# OPEnS-RTC-1_0.net
KiCad netlist of a schematic drawn in EAGLE
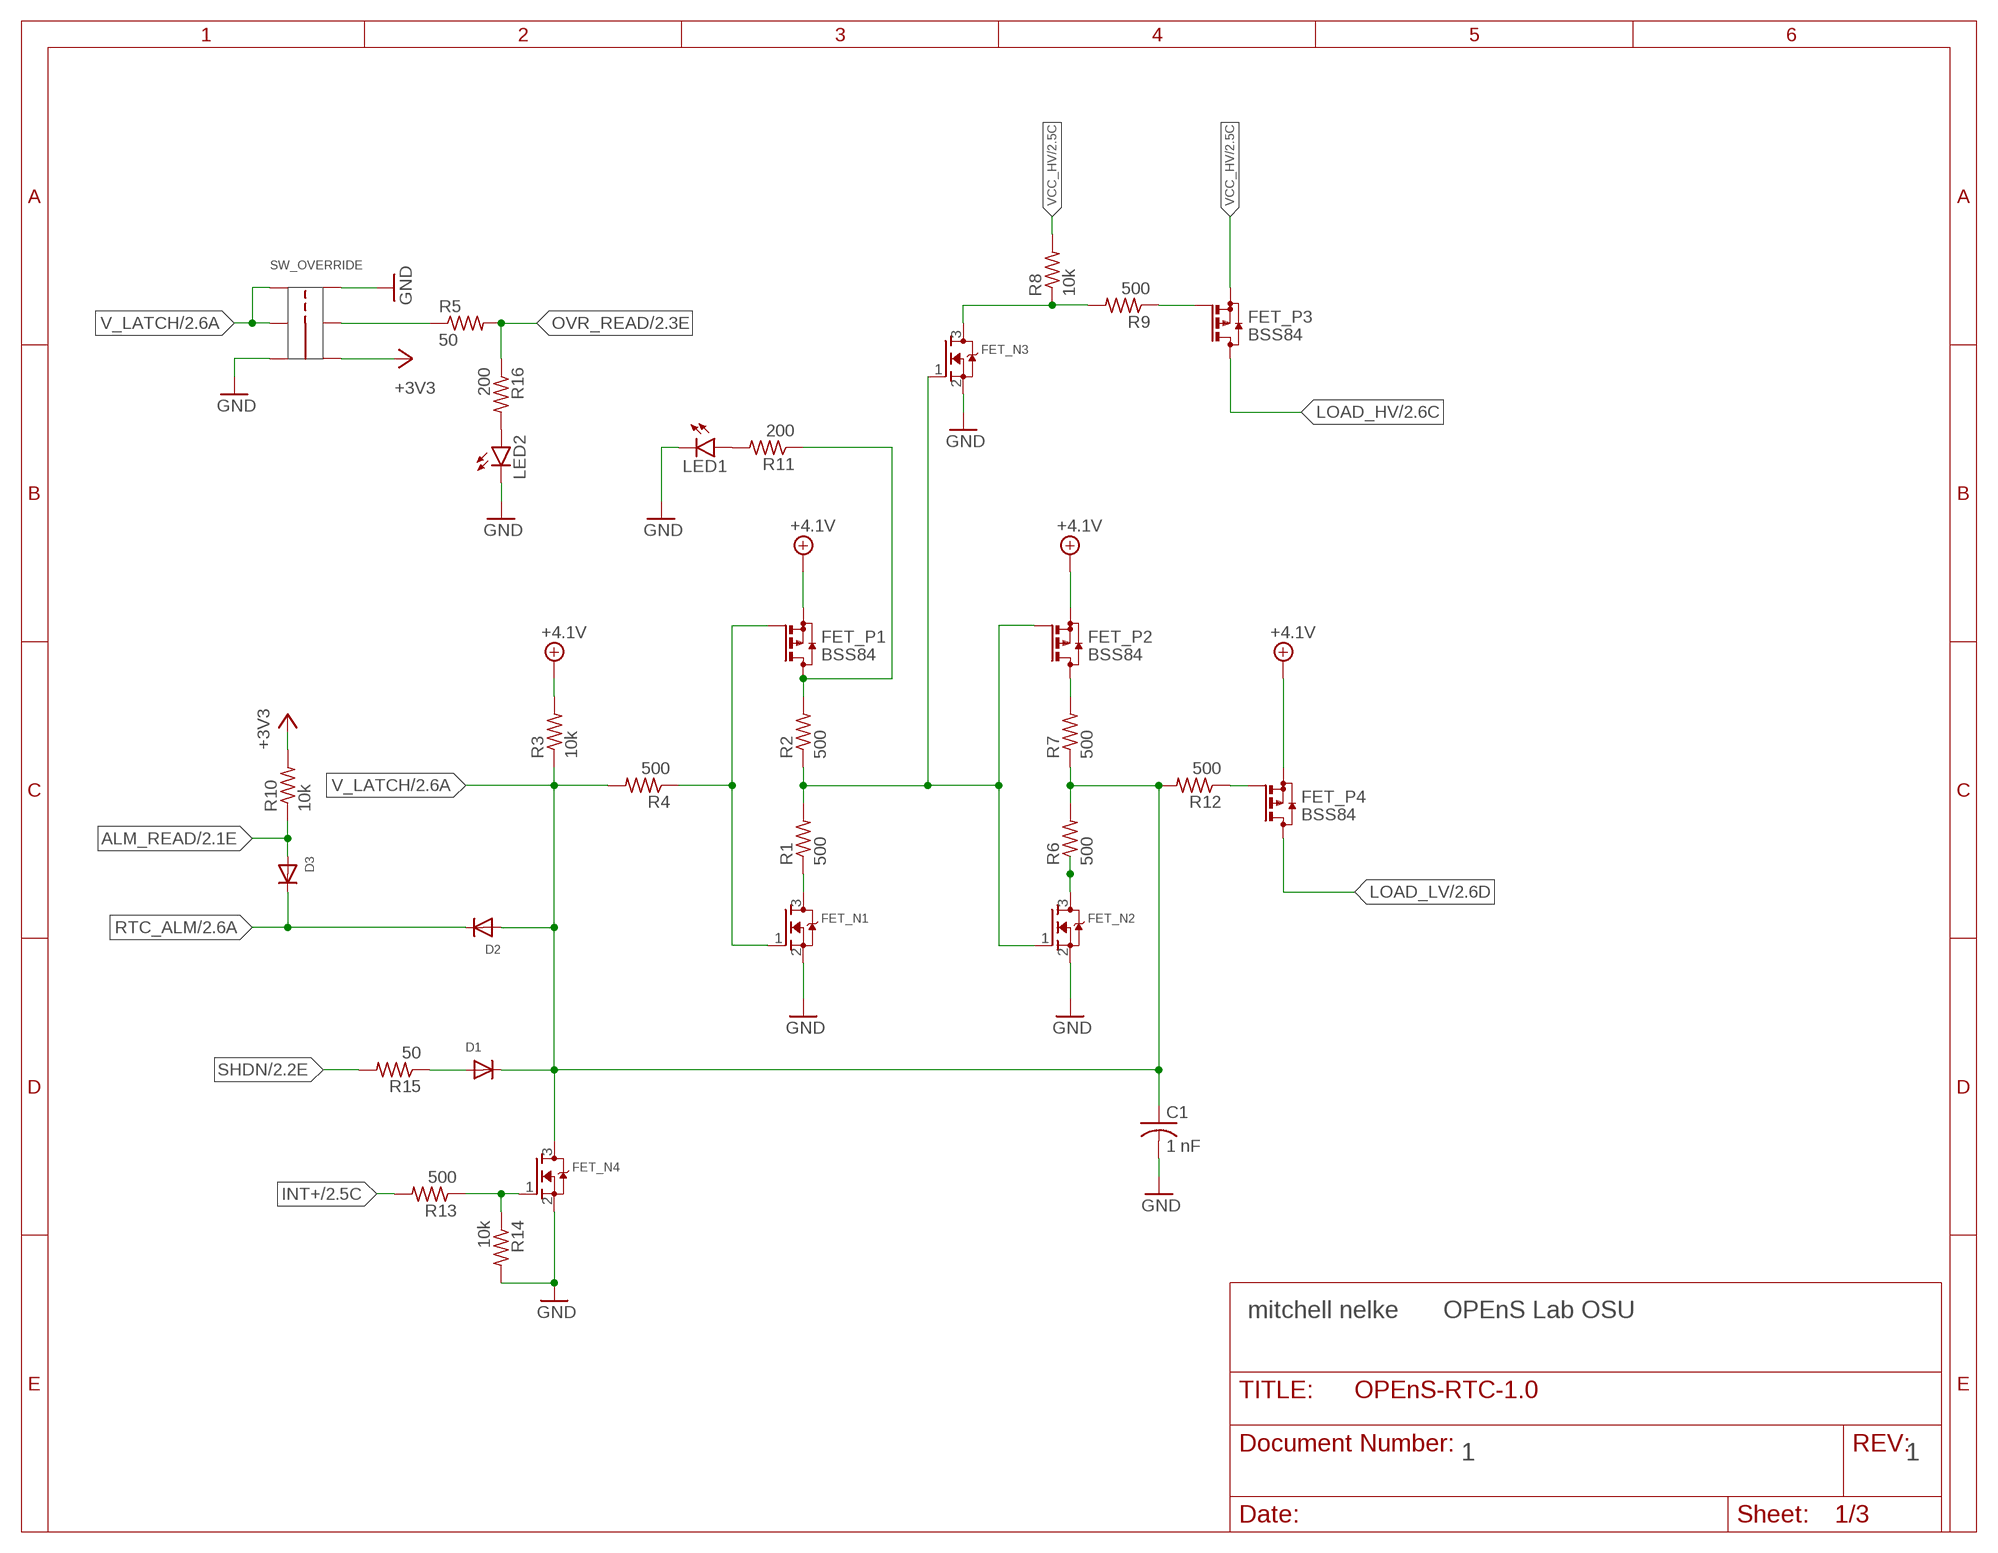
[diagram p0: schematic, sheet 1]
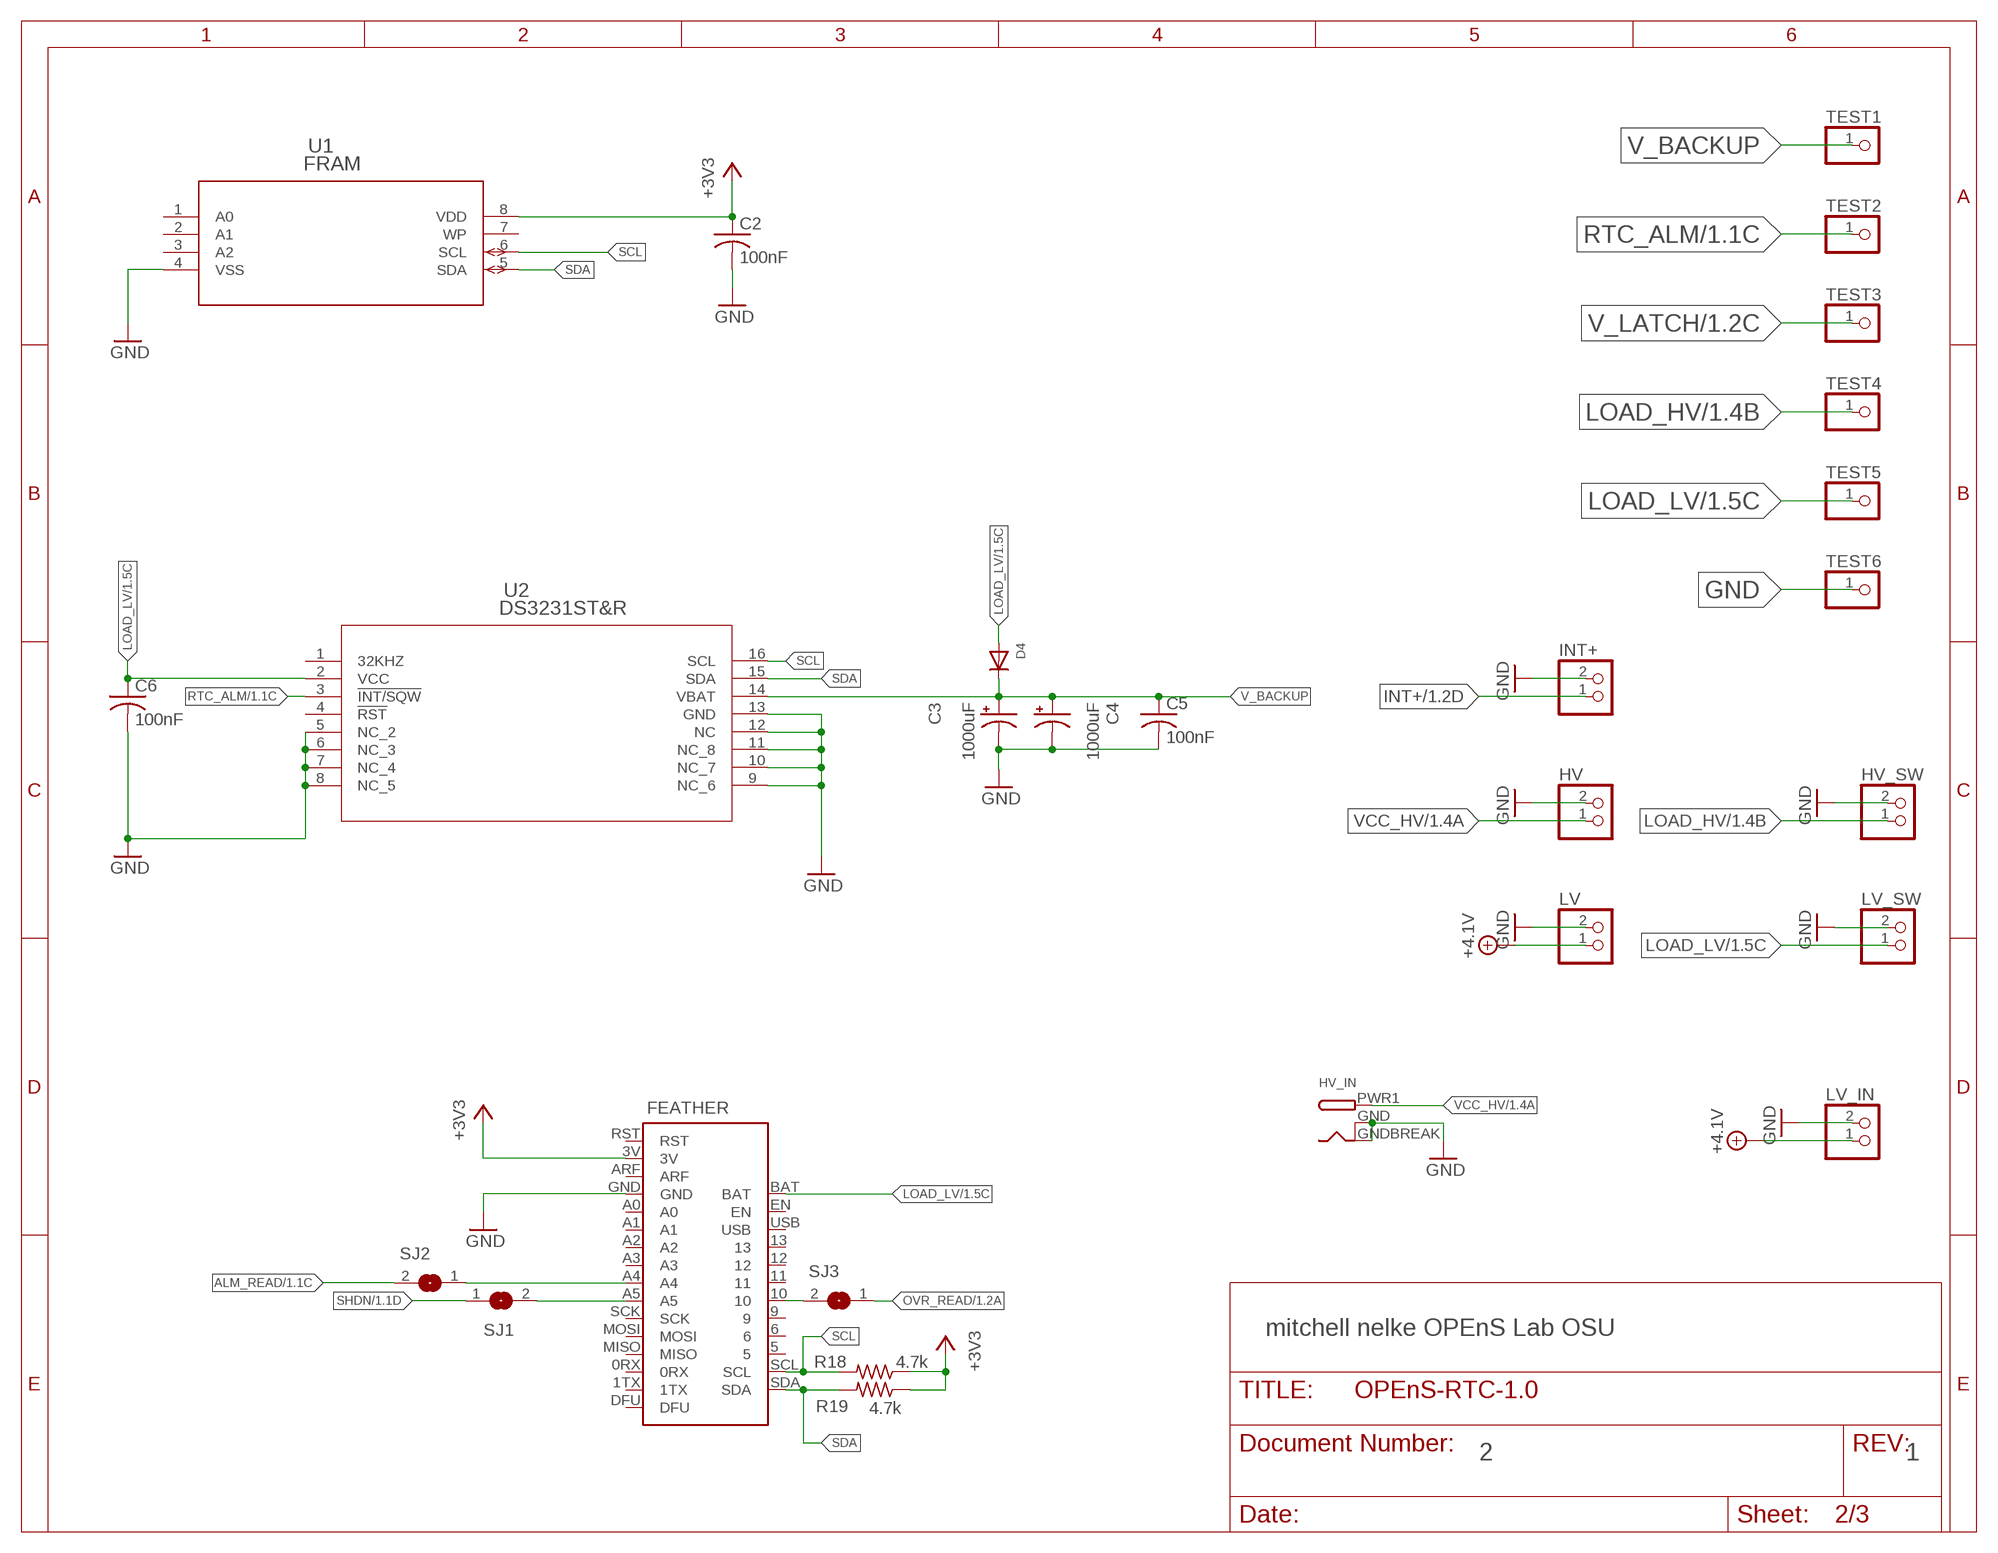
[diagram p1: schematic, sheet 2]

(export (version "E")
  (design (tool "Eeschema 10.0.6"))
  (components
    (comp (ref "C1")
      (value "1 nF")
      (footprint "eagle-import:C0805")
      (libsource (lib "eagle-import") (part "rcl_334_C-USC0805"))
    )
    (comp (ref "D1")
      (value "DIODESOD-123")
      (footprint "eagle-import:SOD-123")
      (libsource (lib "eagle-import") (part "DIODESOD-123"))
    )
    (comp (ref "D2")
      (value "DIODESOD-123")
      (footprint "eagle-import:SOD-123")
      (libsource (lib "eagle-import") (part "DIODESOD-123"))
    )
    (comp (ref "D3")
      (value "DIODESOD-123")
      (footprint "eagle-import:SOD-123")
      (libsource (lib "eagle-import") (part "DIODESOD-123"))
    )
    (comp (ref "FET_N1")
      (value "MOSFET-NREFLOW")
      (footprint "eagle-import:SOT23")
      (libsource (lib "eagle-import") (part "MOSFET-NREFLOW"))
    )
    (comp (ref "FET_N2")
      (value "MOSFET-NREFLOW")
      (footprint "eagle-import:SOT23")
      (libsource (lib "eagle-import") (part "MOSFET-NREFLOW"))
    )
    (comp (ref "FET_N3")
      (value "MOSFET-NREFLOW")
      (footprint "eagle-import:SOT23")
      (libsource (lib "eagle-import") (part "MOSFET-NREFLOW"))
    )
    (comp (ref "FET_N4")
      (value "MOSFET-NREFLOW")
      (footprint "eagle-import:SOT23")
      (libsource (lib "eagle-import") (part "MOSFET-NREFLOW"))
    )
    (comp (ref "FET_P1")
      (value "BSS84")
      (footprint "eagle-import:SOT23")
      (libsource (lib "eagle-import") (part "BSS84"))
    )
    (comp (ref "FET_P2")
      (value "BSS84")
      (footprint "eagle-import:SOT23")
      (libsource (lib "eagle-import") (part "BSS84"))
    )
    (comp (ref "FET_P3")
      (value "BSS84")
      (footprint "eagle-import:SOT23")
      (libsource (lib "eagle-import") (part "BSS84"))
    )
    (comp (ref "FET_P4")
      (value "BSS84")
      (footprint "eagle-import:SOT23")
      (libsource (lib "eagle-import") (part "BSS84"))
    )
    (comp (ref "LED1")
      (value "LEDSMT1206")
      (footprint "eagle-import:1206")
      (libsource (lib "eagle-import") (part "LEDSMT1206"))
    )
    (comp (ref "LED2")
      (value "LEDSMT1206")
      (footprint "eagle-import:1206")
      (libsource (lib "eagle-import") (part "LEDSMT1206"))
    )
    (comp (ref "R1")
      (value "500")
      (footprint "eagle-import:R0805")
      (libsource (lib "eagle-import") (part "rcl_334_R-US_R0805"))
    )
    (comp (ref "R2")
      (value "500")
      (footprint "eagle-import:R0805")
      (libsource (lib "eagle-import") (part "rcl_334_R-US_R0805"))
    )
    (comp (ref "R3")
      (value "10k")
      (footprint "eagle-import:R0805")
      (libsource (lib "eagle-import") (part "rcl_334_R-US_R0805"))
    )
    (comp (ref "R4")
      (value "500")
      (footprint "eagle-import:R0805")
      (libsource (lib "eagle-import") (part "rcl_334_R-US_R0805"))
    )
    (comp (ref "R5")
      (value "50")
      (footprint "eagle-import:R0805")
      (libsource (lib "eagle-import") (part "rcl_334_R-US_R0805"))
    )
    (comp (ref "R6")
      (value "500")
      (footprint "eagle-import:R0805")
      (libsource (lib "eagle-import") (part "rcl_334_R-US_R0805"))
    )
    (comp (ref "R7")
      (value "500")
      (footprint "eagle-import:R0805")
      (libsource (lib "eagle-import") (part "rcl_334_R-US_R0805"))
    )
    (comp (ref "R8")
      (value "10k")
      (footprint "eagle-import:R0805")
      (libsource (lib "eagle-import") (part "rcl_334_R-US_R0805"))
    )
    (comp (ref "R9")
      (value "500")
      (footprint "eagle-import:R0805")
      (libsource (lib "eagle-import") (part "rcl_334_R-US_R0805"))
    )
    (comp (ref "R10")
      (value "10k")
      (footprint "eagle-import:R0805")
      (libsource (lib "eagle-import") (part "rcl_334_R-US_R0805"))
    )
    (comp (ref "R11")
      (value "200")
      (footprint "eagle-import:R0805")
      (libsource (lib "eagle-import") (part "rcl_334_R-US_R0805"))
    )
    (comp (ref "R12")
      (value "500")
      (footprint "eagle-import:R0805")
      (libsource (lib "eagle-import") (part "rcl_334_R-US_R0805"))
    )
    (comp (ref "R13")
      (value "500")
      (footprint "eagle-import:R0805")
      (libsource (lib "eagle-import") (part "rcl_334_R-US_R0805"))
    )
    (comp (ref "R14")
      (value "10k")
      (footprint "eagle-import:R0805")
      (libsource (lib "eagle-import") (part "rcl_334_R-US_R0805"))
    )
    (comp (ref "R15")
      (value "50")
      (footprint "eagle-import:R0805")
      (libsource (lib "eagle-import") (part "rcl_334_R-US_R0805"))
    )
    (comp (ref "R16")
      (value "200")
      (footprint "eagle-import:R0805")
      (libsource (lib "eagle-import") (part "rcl_334_R-US_R0805"))
    )
    (comp (ref "SW_OVERRIDE")
      (value "JS202011JCQN")
      (footprint "eagle-import:VERTICAL_MNT_SMT-J")
      (libsource (lib "eagle-import") (part "JS202011JCQN"))
    )
    (comp (ref "C2")
      (value "100nF")
      (footprint "eagle-import:C0805")
      (libsource (lib "eagle-import") (part "C-USC0805"))
    )
    (comp (ref "C3")
      (value "1000uF")
      (footprint "eagle-import:E3,5-8")
      (libsource (lib "eagle-import") (part "CPOL-USE3.5-8"))
    )
    (comp (ref "C4")
      (value "1000uF")
      (footprint "eagle-import:E3,5-8")
      (libsource (lib "eagle-import") (part "CPOL-USE3.5-8"))
    )
    (comp (ref "C5")
      (value "100nF")
      (footprint "eagle-import:C0805")
      (libsource (lib "eagle-import") (part "C-USC0805"))
    )
    (comp (ref "C6")
      (value "100nF")
      (footprint "eagle-import:C0805")
      (libsource (lib "eagle-import") (part "C-USC0805"))
    )
    (comp (ref "D4")
      (value "DIODESOD-123")
      (footprint "eagle-import:SOD-123")
      (libsource (lib "eagle-import") (part "DIODESOD-123"))
    )
    (comp (ref "FEATHER")
      (value "BLUEFRUIT_M0")
      (footprint "eagle-import:BLUEFRUIT_MO")
      (libsource (lib "eagle-import") (part "BLUEFRUIT_M0"))
    )
    (comp (ref "HV")
      (value "JST_2PIN-SMT")
      (footprint "eagle-import:JST-PH-2-SMT")
      (libsource (lib "eagle-import") (part "JST_2PIN-SMT"))
    )
    (comp (ref "HV_IN")
      (value "DCBARRELSMT")
      (footprint "eagle-import:DCJACK_2MM_SMT")
      (libsource (lib "eagle-import") (part "DCBARRELSMT"))
    )
    (comp (ref "HV_SW")
      (value "JST_2PIN-SMT")
      (footprint "eagle-import:JST-PH-2-SMT")
      (libsource (lib "eagle-import") (part "JST_2PIN-SMT"))
    )
    (comp (ref "INT+")
      (value "JST_2PIN-SMT")
      (footprint "eagle-import:JST-PH-2-SMT")
      (libsource (lib "eagle-import") (part "JST_2PIN-SMT"))
    )
    (comp (ref "LV")
      (value "JST_2PIN-SMT")
      (footprint "eagle-import:JST-PH-2-SMT")
      (libsource (lib "eagle-import") (part "JST_2PIN-SMT"))
    )
    (comp (ref "LV_IN")
      (value "JST_2PIN-SMT")
      (footprint "eagle-import:JST-PH-2-SMT")
      (libsource (lib "eagle-import") (part "JST_2PIN-SMT"))
    )
    (comp (ref "LV_SW")
      (value "JST_2PIN-SMT")
      (footprint "eagle-import:JST-PH-2-SMT")
      (libsource (lib "eagle-import") (part "JST_2PIN-SMT"))
    )
    (comp (ref "R18")
      (value "4.7k")
      (footprint "eagle-import:M0805")
      (libsource (lib "eagle-import") (part "R-US_M0805"))
    )
    (comp (ref "R19")
      (value "4.7k")
      (footprint "eagle-import:M0805")
      (libsource (lib "eagle-import") (part "R-US_M0805"))
    )
    (comp (ref "SJ1") (value "SJ") (footprint "eagle-import:SJ") (libsource (lib "eagle-import") (part "SJ")))
    (comp (ref "SJ2") (value "SJ") (footprint "eagle-import:SJ") (libsource (lib "eagle-import") (part "SJ")))
    (comp (ref "SJ3") (value "SJ") (footprint "eagle-import:SJ") (libsource (lib "eagle-import") (part "SJ")))
    (comp (ref "TEST1")
      (value "PINHD-1X1")
      (footprint "eagle-import:1X01")
      (libsource (lib "eagle-import") (part "PINHD-1X1"))
    )
    (comp (ref "TEST2")
      (value "PINHD-1X1")
      (footprint "eagle-import:1X01")
      (libsource (lib "eagle-import") (part "PINHD-1X1"))
    )
    (comp (ref "TEST3")
      (value "PINHD-1X1")
      (footprint "eagle-import:1X01")
      (libsource (lib "eagle-import") (part "PINHD-1X1"))
    )
    (comp (ref "TEST4")
      (value "PINHD-1X1")
      (footprint "eagle-import:1X01")
      (libsource (lib "eagle-import") (part "PINHD-1X1"))
    )
    (comp (ref "TEST5")
      (value "PINHD-1X1")
      (footprint "eagle-import:1X01")
      (libsource (lib "eagle-import") (part "PINHD-1X1"))
    )
    (comp (ref "TEST6")
      (value "PINHD-1X1")
      (footprint "eagle-import:1X01")
      (libsource (lib "eagle-import") (part "PINHD-1X1"))
    )
    (comp (ref "U1")
      (value "FRAM")
      (footprint "eagle-import:FPT-8P-M02")
      (fields (field (name "MANUFACTURER_PART_NUMBER") "Inc."))
      (libsource (lib "eagle-import") (part "FRAM"))
    )
    (comp (ref "U2")
      (value "DS3231ST&R")
      (footprint "eagle-import:21-0042B_16")
      (fields (field (name "MANUFACTURER_PART_NUMBER") "DS3231S#T&R"))
      (libsource (lib "eagle-import") (part "DS3231ST&R"))
    )
  )
  (nets
    (net (code "1") (name "+3V3") (class "Default")
      (node (ref "C2") (pin "1") (pinfunction "1_1") (pintype "passive"))
      (node (ref "FEATHER") (pin "3V") (pinfunction "3V_3V") (pintype "bidirectional"))
      (node (ref "R10") (pin "2") (pinfunction "2_2") (pintype "passive"))
      (node (ref "R18") (pin "1") (pinfunction "1_1") (pintype "passive"))
      (node (ref "R19") (pin "1") (pinfunction "1_1") (pintype "passive"))
      (node (ref "SW_OVERRIDE") (pin "A_") (pinfunction "A__A_") (pintype "bidirectional"))
      (node (ref "U1") (pin "8") (pinfunction "VDD_8") (pintype "power_in"))
    )
    (net (code "2") (name "+4.1V") (class "Default")
      (node (ref "FET_P1") (pin "2") (pinfunction "S_2") (pintype "passive"))
      (node (ref "FET_P2") (pin "2") (pinfunction "S_2") (pintype "passive"))
      (node (ref "FET_P4") (pin "2") (pinfunction "S_2") (pintype "passive"))
      (node (ref "LV") (pin "1") (pinfunction "2_1") (pintype "passive"))
      (node (ref "LV_IN") (pin "1") (pinfunction "2_1") (pintype "passive"))
      (node (ref "R3") (pin "2") (pinfunction "2_2") (pintype "passive"))
    )
    (net (code "3") (name "ALM_READ") (class "Default")
      (node (ref "D3") (pin "A") (pinfunction "A_A") (pintype "passive"))
      (node (ref "R10") (pin "1") (pinfunction "1_1") (pintype "passive"))
      (node (ref "SJ2") (pin "2") (pinfunction "2_2") (pintype "passive"))
    )
    (net (code "4") (name "GND") (class "Default")
      (node (ref "C1") (pin "2") (pinfunction "2_2") (pintype "passive"))
      (node (ref "C2") (pin "2") (pinfunction "2_2") (pintype "passive"))
      (node (ref "C3") (pin "-") (pinfunction "-_-") (pintype "passive"))
      (node (ref "C4") (pin "-") (pinfunction "-_-") (pintype "passive"))
      (node (ref "C5") (pin "2") (pinfunction "2_2") (pintype "passive"))
      (node (ref "C6") (pin "2") (pinfunction "2_2") (pintype "passive"))
      (node (ref "FEATHER") (pin "GND") (pinfunction "GND_GND") (pintype "bidirectional"))
      (node (ref "FET_N1") (pin "2") (pinfunction "S_2") (pintype "bidirectional"))
      (node (ref "FET_N2") (pin "2") (pinfunction "S_2") (pintype "bidirectional"))
      (node (ref "FET_N3") (pin "2") (pinfunction "S_2") (pintype "bidirectional"))
      (node (ref "FET_N4") (pin "2") (pinfunction "S_2") (pintype "bidirectional"))
      (node (ref "HV") (pin "2") (pinfunction "1_2") (pintype "passive"))
      (node (ref "HV_IN") (pin "GND") (pinfunction "GNDBREAK_GND") (pintype "power_in"))
      (node (ref "HV_IN") (pin "GNDBREAK") (pinfunction "GND_GNDBREAK") (pintype "power_in"))
      (node (ref "HV_SW") (pin "2") (pinfunction "1_2") (pintype "passive"))
      (node (ref "INT+") (pin "2") (pinfunction "1_2") (pintype "passive"))
      (node (ref "LED1") (pin "C") (pinfunction "C_C") (pintype "passive"))
      (node (ref "LED2") (pin "C") (pinfunction "C_C") (pintype "passive"))
      (node (ref "LV") (pin "2") (pinfunction "1_2") (pintype "passive"))
      (node (ref "LV_IN") (pin "2") (pinfunction "1_2") (pintype "passive"))
      (node (ref "LV_SW") (pin "2") (pinfunction "1_2") (pintype "passive"))
      (node (ref "R14") (pin "2") (pinfunction "2_2") (pintype "passive"))
      (node (ref "SW_OVERRIDE") (pin "A") (pinfunction "A_A") (pintype "bidirectional"))
      (node (ref "SW_OVERRIDE") (pin "B_") (pinfunction "B__B_") (pintype "bidirectional"))
      (node (ref "TEST6") (pin "1") (pinfunction "1_1") (pintype "passive"))
      (node (ref "U1") (pin "4") (pinfunction "VSS_4") (pintype "power_in"))
      (node (ref "U2") (pin "10") (pinfunction "NC_7_10") (pintype "passive"))
      (node (ref "U2") (pin "11") (pinfunction "NC_8_11") (pintype "passive"))
      (node (ref "U2") (pin "12") (pinfunction "NC_12") (pintype "passive"))
      (node (ref "U2") (pin "13") (pinfunction "GND_13") (pintype "power_in"))
      (node (ref "U2") (pin "5") (pinfunction "NC_2_5") (pintype "passive"))
      (node (ref "U2") (pin "6") (pinfunction "NC_3_6") (pintype "passive"))
      (node (ref "U2") (pin "7") (pinfunction "NC_4_7") (pintype "passive"))
      (node (ref "U2") (pin "8") (pinfunction "NC_5_8") (pintype "passive"))
      (node (ref "U2") (pin "9") (pinfunction "NC_6_9") (pintype "passive"))
    )
    (net (code "5") (name "INT+") (class "Default")
      (node (ref "INT+") (pin "1") (pinfunction "2_1") (pintype "passive"))
      (node (ref "R13") (pin "2") (pinfunction "2_2") (pintype "passive"))
    )
    (net (code "6") (name "LOAD_HV") (class "Default")
      (node (ref "FET_P3") (pin "3") (pinfunction "D_3") (pintype "passive"))
      (node (ref "HV_SW") (pin "1") (pinfunction "2_1") (pintype "passive"))
      (node (ref "TEST4") (pin "1") (pinfunction "1_1") (pintype "passive"))
    )
    (net (code "7") (name "LOAD_LV") (class "Default")
      (node (ref "C6") (pin "1") (pinfunction "1_1") (pintype "passive"))
      (node (ref "D4") (pin "A") (pinfunction "A_A") (pintype "passive"))
      (node (ref "FEATHER") (pin "BAT") (pinfunction "BAT_BAT") (pintype "bidirectional"))
      (node (ref "FET_P4") (pin "3") (pinfunction "D_3") (pintype "passive"))
      (node (ref "LV_SW") (pin "1") (pinfunction "2_1") (pintype "passive"))
      (node (ref "TEST5") (pin "1") (pinfunction "1_1") (pintype "passive"))
      (node (ref "U2") (pin "2") (pinfunction "VCC_2") (pintype "power_in"))
    )
    (net (code "8") (name "Net-(D1-PadA)") (class "Default")
      (node (ref "D1") (pin "A") (pinfunction "A_A") (pintype "passive"))
      (node (ref "R15") (pin "1") (pinfunction "1_1") (pintype "passive"))
    )
    (net (code "9") (name "Net-(FEATHER-Pad10)") (class "Default")
      (node (ref "FEATHER") (pin "10") (pinfunction "10_10") (pintype "bidirectional"))
      (node (ref "SJ3") (pin "2") (pinfunction "2_2") (pintype "passive"))
    )
    (net (code "10") (name "Net-(FEATHER-PadA4)") (class "Default")
      (node (ref "FEATHER") (pin "A4") (pinfunction "A4_A4") (pintype "bidirectional"))
      (node (ref "SJ2") (pin "1") (pinfunction "1_1") (pintype "passive"))
    )
    (net (code "11") (name "Net-(FEATHER-PadA5)") (class "Default")
      (node (ref "FEATHER") (pin "A5") (pinfunction "A5_A5") (pintype "bidirectional"))
      (node (ref "SJ1") (pin "2") (pinfunction "2_2") (pintype "passive"))
    )
    (net (code "12") (name "Net-(FET_N1-D)") (class "Default")
      (node (ref "FET_N1") (pin "3") (pinfunction "D_3") (pintype "bidirectional"))
      (node (ref "R1") (pin "1") (pinfunction "1_1") (pintype "passive"))
    )
    (net (code "13") (name "Net-(FET_N1-G)") (class "Default")
      (node (ref "FET_N1") (pin "1") (pinfunction "G_1") (pintype "bidirectional"))
      (node (ref "FET_P1") (pin "1") (pinfunction "G_1") (pintype "passive"))
      (node (ref "R4") (pin "1") (pinfunction "1_1") (pintype "passive"))
    )
    (net (code "14") (name "Net-(FET_N2-D)") (class "Default")
      (node (ref "FET_N2") (pin "3") (pinfunction "D_3") (pintype "bidirectional"))
      (node (ref "R6") (pin "1") (pinfunction "1_1") (pintype "passive"))
    )
    (net (code "15") (name "Net-(FET_N2-G)") (class "Default")
      (node (ref "FET_N2") (pin "1") (pinfunction "G_1") (pintype "bidirectional"))
      (node (ref "FET_N3") (pin "1") (pinfunction "G_1") (pintype "bidirectional"))
      (node (ref "FET_P2") (pin "1") (pinfunction "G_1") (pintype "passive"))
      (node (ref "R1") (pin "2") (pinfunction "2_2") (pintype "passive"))
      (node (ref "R2") (pin "1") (pinfunction "1_1") (pintype "passive"))
    )
    (net (code "16") (name "Net-(FET_N3-D)") (class "Default")
      (node (ref "FET_N3") (pin "3") (pinfunction "D_3") (pintype "bidirectional"))
      (node (ref "R8") (pin "1") (pinfunction "1_1") (pintype "passive"))
      (node (ref "R9") (pin "2") (pinfunction "2_2") (pintype "passive"))
    )
    (net (code "17") (name "Net-(FET_N4-G)") (class "Default")
      (node (ref "FET_N4") (pin "1") (pinfunction "G_1") (pintype "bidirectional"))
      (node (ref "R13") (pin "1") (pinfunction "1_1") (pintype "passive"))
      (node (ref "R14") (pin "1") (pinfunction "1_1") (pintype "passive"))
    )
    (net (code "18") (name "Net-(FET_P1-D)") (class "Default")
      (node (ref "FET_P1") (pin "3") (pinfunction "D_3") (pintype "passive"))
      (node (ref "R11") (pin "1") (pinfunction "1_1") (pintype "passive"))
      (node (ref "R2") (pin "2") (pinfunction "2_2") (pintype "passive"))
    )
    (net (code "19") (name "Net-(FET_P2-D)") (class "Default")
      (node (ref "FET_P2") (pin "3") (pinfunction "D_3") (pintype "passive"))
      (node (ref "R7") (pin "2") (pinfunction "2_2") (pintype "passive"))
    )
    (net (code "20") (name "Net-(FET_P3-G)") (class "Default")
      (node (ref "FET_P3") (pin "1") (pinfunction "G_1") (pintype "passive"))
      (node (ref "R9") (pin "1") (pinfunction "1_1") (pintype "passive"))
    )
    (net (code "21") (name "Net-(FET_P4-G)") (class "Default")
      (node (ref "FET_P4") (pin "1") (pinfunction "G_1") (pintype "passive"))
      (node (ref "R12") (pin "1") (pinfunction "1_1") (pintype "passive"))
    )
    (net (code "22") (name "Net-(LED1-PadA)") (class "Default")
      (node (ref "LED1") (pin "A") (pinfunction "A_A") (pintype "passive"))
      (node (ref "R11") (pin "2") (pinfunction "2_2") (pintype "passive"))
    )
    (net (code "23") (name "Net-(LED2-PadA)") (class "Default")
      (node (ref "LED2") (pin "A") (pinfunction "A_A") (pintype "passive"))
      (node (ref "R16") (pin "2") (pinfunction "2_2") (pintype "passive"))
    )
    (net (code "24") (name "Net-(R5-Pad1)") (class "Default")
      (node (ref "R5") (pin "1") (pinfunction "1_1") (pintype "passive"))
      (node (ref "SW_OVERRIDE") (pin "COM_") (pinfunction "COM__COM_") (pintype "bidirectional"))
    )
    (net (code "25") (name "OVR_READ") (class "Default")
      (node (ref "R16") (pin "1") (pinfunction "1_1") (pintype "passive"))
      (node (ref "R5") (pin "2") (pinfunction "2_2") (pintype "passive"))
      (node (ref "SJ3") (pin "1") (pinfunction "1_1") (pintype "passive"))
    )
    (net (code "26") (name "RTC_ALM") (class "Default")
      (node (ref "D2") (pin "C") (pinfunction "C_C") (pintype "passive"))
      (node (ref "D3") (pin "C") (pinfunction "C_C") (pintype "passive"))
      (node (ref "TEST2") (pin "1") (pinfunction "1_1") (pintype "passive"))
      (node (ref "U2") (pin "3") (pinfunction "~{INT/SQW}_3") (pintype "passive"))
    )
    (net (code "27") (name "SCL") (class "Default")
      (node (ref "FEATHER") (pin "SCL") (pinfunction "SCL_SCL") (pintype "bidirectional"))
      (node (ref "R18") (pin "2") (pinfunction "2_2") (pintype "passive"))
      (node (ref "U1") (pin "6") (pinfunction "SCL_6") (pintype "bidirectional"))
      (node (ref "U2") (pin "16") (pinfunction "SCL_16") (pintype "passive"))
    )
    (net (code "28") (name "SDA") (class "Default")
      (node (ref "FEATHER") (pin "SDA") (pinfunction "SDA_SDA") (pintype "bidirectional"))
      (node (ref "R19") (pin "2") (pinfunction "2_2") (pintype "passive"))
      (node (ref "U1") (pin "5") (pinfunction "SDA_5") (pintype "bidirectional"))
      (node (ref "U2") (pin "15") (pinfunction "SDA_15") (pintype "passive"))
    )
    (net (code "29") (name "SHDN") (class "Default")
      (node (ref "R15") (pin "2") (pinfunction "2_2") (pintype "passive"))
      (node (ref "SJ1") (pin "1") (pinfunction "1_1") (pintype "passive"))
    )
    (net (code "30") (name "VCC_HV") (class "Default")
      (node (ref "FET_P3") (pin "2") (pinfunction "S_2") (pintype "passive"))
      (node (ref "HV") (pin "1") (pinfunction "2_1") (pintype "passive"))
      (node (ref "HV_IN") (pin "PWR1") (pinfunction "PWR_PWR1") (pintype "power_in"))
      (node (ref "R8") (pin "2") (pinfunction "2_2") (pintype "passive"))
    )
    (net (code "31") (name "V_BACKUP") (class "Default")
      (node (ref "C3") (pin "+") (pinfunction "+_+") (pintype "passive"))
      (node (ref "C4") (pin "+") (pinfunction "+_+") (pintype "passive"))
      (node (ref "C5") (pin "1") (pinfunction "1_1") (pintype "passive"))
      (node (ref "D4") (pin "C") (pinfunction "C_C") (pintype "passive"))
      (node (ref "TEST1") (pin "1") (pinfunction "1_1") (pintype "passive"))
      (node (ref "U2") (pin "14") (pinfunction "VBAT_14") (pintype "power_in"))
    )
    (net (code "32") (name "V_LATCH") (class "Default")
      (node (ref "C1") (pin "1") (pinfunction "1_1") (pintype "passive"))
      (node (ref "D1") (pin "C") (pinfunction "C_C") (pintype "passive"))
      (node (ref "D2") (pin "A") (pinfunction "A_A") (pintype "passive"))
      (node (ref "FET_N4") (pin "3") (pinfunction "D_3") (pintype "bidirectional"))
      (node (ref "R12") (pin "2") (pinfunction "2_2") (pintype "passive"))
      (node (ref "R3") (pin "1") (pinfunction "1_1") (pintype "passive"))
      (node (ref "R4") (pin "2") (pinfunction "2_2") (pintype "passive"))
      (node (ref "R6") (pin "2") (pinfunction "2_2") (pintype "passive"))
      (node (ref "R7") (pin "1") (pinfunction "1_1") (pintype "passive"))
      (node (ref "SW_OVERRIDE") (pin "B") (pinfunction "B_B") (pintype "bidirectional"))
      (node (ref "SW_OVERRIDE") (pin "COM") (pinfunction "COM_COM") (pintype "bidirectional"))
      (node (ref "TEST3") (pin "1") (pinfunction "1_1") (pintype "passive"))
    )
    (net (code "33") (name "unconnected-(FEATHER-Pad0RX)") (class "Default")
      (node (ref "FEATHER") (pin "0RX") (pinfunction "0RX_0RX") (pintype "bidirectional"))
    )
    (net (code "34") (name "unconnected-(FEATHER-Pad1TX)") (class "Default")
      (node (ref "FEATHER") (pin "1TX") (pinfunction "1TX_1TX") (pintype "bidirectional"))
    )
    (net (code "35") (name "unconnected-(FEATHER-Pad5)") (class "Default")
      (node (ref "FEATHER") (pin "5") (pinfunction "5_5") (pintype "bidirectional"))
    )
    (net (code "36") (name "unconnected-(FEATHER-Pad6)") (class "Default")
      (node (ref "FEATHER") (pin "6") (pinfunction "6_6") (pintype "bidirectional"))
    )
    (net (code "37") (name "unconnected-(FEATHER-Pad9)") (class "Default")
      (node (ref "FEATHER") (pin "9") (pinfunction "9_9") (pintype "bidirectional"))
    )
    (net (code "38") (name "unconnected-(FEATHER-Pad11)") (class "Default")
      (node (ref "FEATHER") (pin "11") (pinfunction "11_11") (pintype "bidirectional"))
    )
    (net (code "39") (name "unconnected-(FEATHER-Pad12)") (class "Default")
      (node (ref "FEATHER") (pin "12") (pinfunction "12_12") (pintype "bidirectional"))
    )
    (net (code "40") (name "unconnected-(FEATHER-Pad13)") (class "Default")
      (node (ref "FEATHER") (pin "13") (pinfunction "13_13") (pintype "bidirectional"))
    )
    (net (code "41") (name "unconnected-(FEATHER-PadA0)") (class "Default")
      (node (ref "FEATHER") (pin "A0") (pinfunction "A0_A0") (pintype "bidirectional"))
    )
    (net (code "42") (name "unconnected-(FEATHER-PadA1)") (class "Default")
      (node (ref "FEATHER") (pin "A1") (pinfunction "A1_A1") (pintype "bidirectional"))
    )
    (net (code "43") (name "unconnected-(FEATHER-PadA2)") (class "Default")
      (node (ref "FEATHER") (pin "A2") (pinfunction "A2_A2") (pintype "bidirectional"))
    )
    (net (code "44") (name "unconnected-(FEATHER-PadA3)") (class "Default")
      (node (ref "FEATHER") (pin "A3") (pinfunction "A3_A3") (pintype "bidirectional"))
    )
    (net (code "45") (name "unconnected-(FEATHER-PadARF)") (class "Default")
      (node (ref "FEATHER") (pin "ARF") (pinfunction "ARF_ARF") (pintype "bidirectional"))
    )
    (net (code "46") (name "unconnected-(FEATHER-PadDFU)") (class "Default")
      (node (ref "FEATHER") (pin "DFU") (pinfunction "DFU_DFU") (pintype "bidirectional"))
    )
    (net (code "47") (name "unconnected-(FEATHER-PadEN)") (class "Default")
      (node (ref "FEATHER") (pin "EN") (pinfunction "EN_EN") (pintype "bidirectional"))
    )
    (net (code "48") (name "unconnected-(FEATHER-PadMISO)") (class "Default")
      (node (ref "FEATHER") (pin "MISO") (pinfunction "MISO_MISO") (pintype "bidirectional"))
    )
    (net (code "49") (name "unconnected-(FEATHER-PadMOSI)") (class "Default")
      (node (ref "FEATHER") (pin "MOSI") (pinfunction "MOSI_MOSI") (pintype "bidirectional"))
    )
    (net (code "50") (name "unconnected-(FEATHER-PadRST)") (class "Default")
      (node (ref "FEATHER") (pin "RST") (pinfunction "RST_RST") (pintype "bidirectional"))
    )
    (net (code "51") (name "unconnected-(FEATHER-PadSCK)") (class "Default")
      (node (ref "FEATHER") (pin "SCK") (pinfunction "SCK_SCK") (pintype "bidirectional"))
    )
    (net (code "52") (name "unconnected-(FEATHER-PadUSB)") (class "Default")
      (node (ref "FEATHER") (pin "USB") (pinfunction "USB_USB") (pintype "bidirectional"))
    )
    (net (code "53") (name "unconnected-(U1-A0-Pad1)") (class "Default")
      (node (ref "U1") (pin "1") (pinfunction "A0_1") (pintype "passive"))
    )
    (net (code "54") (name "unconnected-(U1-A1-Pad2)") (class "Default")
      (node (ref "U1") (pin "2") (pinfunction "A1_2") (pintype "passive"))
    )
    (net (code "55") (name "unconnected-(U1-A2-Pad3)") (class "Default")
      (node (ref "U1") (pin "3") (pinfunction "A2_3") (pintype "passive"))
    )
    (net (code "56") (name "unconnected-(U1-WP-Pad7)") (class "Default")
      (node (ref "U1") (pin "7") (pinfunction "WP_7") (pintype "passive"))
    )
    (net (code "57") (name "unconnected-(U2-32KHZ-Pad1)") (class "Default")
      (node (ref "U2") (pin "1") (pinfunction "32KHZ_1") (pintype "passive"))
    )
    (net (code "58") (name "unconnected-(U2-~{RST}-Pad4)") (class "Default")
      (node (ref "U2") (pin "4") (pinfunction "~{RST}_4") (pintype "passive"))
    )
  )
)
